# IcosaStellaMedallion.net
KiCad netlist of a schematic drawn in EAGLE
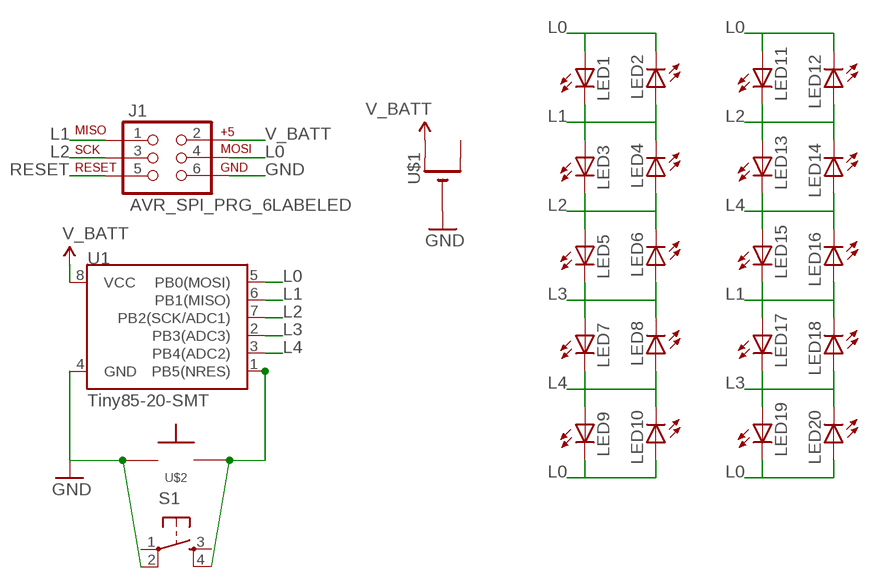
[diagram p0: schematic, sheet 1]

(export (version "E")
  (design (tool "Eeschema 10.0.6"))
  (components
    (comp (ref "J1")
      (value "AVR_SPI_PRG_6LABELED")
      (footprint "eagle-import:2X3-NS")
      (libsource (lib "eagle-import") (part "AVR_SPI_PRG_6LABELED"))
    )
    (comp (ref "LED1")
      (value "LED5MM")
      (footprint "eagle-import:LED5MM")
      (libsource (lib "eagle-import") (part "LED5MM"))
    )
    (comp (ref "LED2")
      (value "LED5MM")
      (footprint "eagle-import:LED5MM")
      (libsource (lib "eagle-import") (part "LED5MM"))
    )
    (comp (ref "LED3")
      (value "LED5MM")
      (footprint "eagle-import:LED5MM")
      (libsource (lib "eagle-import") (part "LED5MM"))
    )
    (comp (ref "LED4")
      (value "LED5MM")
      (footprint "eagle-import:LED5MM")
      (libsource (lib "eagle-import") (part "LED5MM"))
    )
    (comp (ref "LED5")
      (value "LED5MM")
      (footprint "eagle-import:LED5MM")
      (libsource (lib "eagle-import") (part "LED5MM"))
    )
    (comp (ref "LED6")
      (value "LED5MM")
      (footprint "eagle-import:LED5MM")
      (libsource (lib "eagle-import") (part "LED5MM"))
    )
    (comp (ref "LED7")
      (value "LED5MM")
      (footprint "eagle-import:LED5MM")
      (libsource (lib "eagle-import") (part "LED5MM"))
    )
    (comp (ref "LED8")
      (value "LED5MM")
      (footprint "eagle-import:LED5MM")
      (libsource (lib "eagle-import") (part "LED5MM"))
    )
    (comp (ref "LED9")
      (value "LED5MM")
      (footprint "eagle-import:LED5MM")
      (libsource (lib "eagle-import") (part "LED5MM"))
    )
    (comp (ref "LED10")
      (value "LED5MM")
      (footprint "eagle-import:LED5MM")
      (libsource (lib "eagle-import") (part "LED5MM"))
    )
    (comp (ref "LED11")
      (value "LED5MM")
      (footprint "eagle-import:LED5MM")
      (libsource (lib "eagle-import") (part "LED5MM"))
    )
    (comp (ref "LED12")
      (value "LED5MM")
      (footprint "eagle-import:LED5MM")
      (libsource (lib "eagle-import") (part "LED5MM"))
    )
    (comp (ref "LED13")
      (value "LED5MM")
      (footprint "eagle-import:LED5MM")
      (libsource (lib "eagle-import") (part "LED5MM"))
    )
    (comp (ref "LED14")
      (value "LED5MM")
      (footprint "eagle-import:LED5MM")
      (libsource (lib "eagle-import") (part "LED5MM"))
    )
    (comp (ref "LED15")
      (value "LED5MM")
      (footprint "eagle-import:LED5MM")
      (libsource (lib "eagle-import") (part "LED5MM"))
    )
    (comp (ref "LED16")
      (value "LED5MM")
      (footprint "eagle-import:LED5MM")
      (libsource (lib "eagle-import") (part "LED5MM"))
    )
    (comp (ref "LED17")
      (value "LED5MM")
      (footprint "eagle-import:LED5MM")
      (libsource (lib "eagle-import") (part "LED5MM"))
    )
    (comp (ref "LED18")
      (value "LED5MM")
      (footprint "eagle-import:LED5MM")
      (libsource (lib "eagle-import") (part "LED5MM"))
    )
    (comp (ref "LED19")
      (value "LED5MM")
      (footprint "eagle-import:LED5MM")
      (libsource (lib "eagle-import") (part "LED5MM"))
    )
    (comp (ref "LED20")
      (value "LED5MM")
      (footprint "eagle-import:LED5MM")
      (libsource (lib "eagle-import") (part "LED5MM"))
    )
    (comp (ref "S1")
      (value "TAC_SWITCHSMD")
      (footprint "eagle-import:TACTILE-SWITCH-SMD")
      (libsource (lib "eagle-import") (part "TAC_SWITCHSMD"))
    )
    (comp (ref "U$1")
      (value "CR2032THM")
      (footprint "eagle-import:CR2032-THRU")
      (libsource (lib "eagle-import") (part "CR2032THM"))
    )
    (comp (ref "U$2")
      (value "TAC_SPST_NOSMD")
      (footprint "eagle-import:KXT")
      (libsource (lib "eagle-import") (part "TAC_SPST_NOSMD"))
    )
    (comp (ref "U1")
      (value "Tiny85-20-SMT")
      (footprint "eagle-import:SO08-EIAJ")
      (libsource (lib "eagle-import") (part "ATTINY45TINY85-20-SMT"))
    )
  )
  (nets
    (net (code "1") (name "/L0") (class "Default")
      (node (ref "J1") (pin "4") (pinfunction "MOSI_4") (pintype "passive"))
      (node (ref "LED1") (pin "A") (pinfunction "A_A") (pintype "passive"))
      (node (ref "LED10") (pin "A") (pinfunction "A_A") (pintype "passive"))
      (node (ref "LED11") (pin "A") (pinfunction "A_A") (pintype "passive"))
      (node (ref "LED12") (pin "K") (pinfunction "C_K") (pintype "passive"))
      (node (ref "LED19") (pin "K") (pinfunction "C_K") (pintype "passive"))
      (node (ref "LED2") (pin "K") (pinfunction "C_K") (pintype "passive"))
      (node (ref "LED20") (pin "A") (pinfunction "A_A") (pintype "passive"))
      (node (ref "LED9") (pin "K") (pinfunction "C_K") (pintype "passive"))
      (node (ref "U1") (pin "5") (pinfunction "PB0(MOSI)_5") (pintype "bidirectional"))
    )
    (net (code "2") (name "/L1") (class "Default")
      (node (ref "J1") (pin "1") (pinfunction "MISO_1") (pintype "passive"))
      (node (ref "LED1") (pin "K") (pinfunction "C_K") (pintype "passive"))
      (node (ref "LED15") (pin "K") (pinfunction "C_K") (pintype "passive"))
      (node (ref "LED16") (pin "A") (pinfunction "A_A") (pintype "passive"))
      (node (ref "LED17") (pin "A") (pinfunction "A_A") (pintype "passive"))
      (node (ref "LED18") (pin "K") (pinfunction "C_K") (pintype "passive"))
      (node (ref "LED2") (pin "A") (pinfunction "A_A") (pintype "passive"))
      (node (ref "LED3") (pin "A") (pinfunction "A_A") (pintype "passive"))
      (node (ref "LED4") (pin "K") (pinfunction "C_K") (pintype "passive"))
      (node (ref "U1") (pin "6") (pinfunction "PB1(MISO)_6") (pintype "bidirectional"))
    )
    (net (code "3") (name "/L2") (class "Default")
      (node (ref "J1") (pin "3") (pinfunction "SCK_3") (pintype "passive"))
      (node (ref "LED11") (pin "K") (pinfunction "C_K") (pintype "passive"))
      (node (ref "LED12") (pin "A") (pinfunction "A_A") (pintype "passive"))
      (node (ref "LED13") (pin "A") (pinfunction "A_A") (pintype "passive"))
      (node (ref "LED14") (pin "K") (pinfunction "C_K") (pintype "passive"))
      (node (ref "LED3") (pin "K") (pinfunction "C_K") (pintype "passive"))
      (node (ref "LED4") (pin "A") (pinfunction "A_A") (pintype "passive"))
      (node (ref "LED5") (pin "A") (pinfunction "A_A") (pintype "passive"))
      (node (ref "LED6") (pin "K") (pinfunction "C_K") (pintype "passive"))
      (node (ref "U1") (pin "7") (pinfunction "PB2(SCK/ADC1)_7") (pintype "bidirectional"))
    )
    (net (code "4") (name "/L3") (class "Default")
      (node (ref "LED17") (pin "K") (pinfunction "C_K") (pintype "passive"))
      (node (ref "LED18") (pin "A") (pinfunction "A_A") (pintype "passive"))
      (node (ref "LED19") (pin "A") (pinfunction "A_A") (pintype "passive"))
      (node (ref "LED20") (pin "K") (pinfunction "C_K") (pintype "passive"))
      (node (ref "LED5") (pin "K") (pinfunction "C_K") (pintype "passive"))
      (node (ref "LED6") (pin "A") (pinfunction "A_A") (pintype "passive"))
      (node (ref "LED7") (pin "A") (pinfunction "A_A") (pintype "passive"))
      (node (ref "LED8") (pin "K") (pinfunction "C_K") (pintype "passive"))
      (node (ref "U1") (pin "2") (pinfunction "PB3(ADC3)_2") (pintype "bidirectional"))
    )
    (net (code "5") (name "/L4") (class "Default")
      (node (ref "LED10") (pin "K") (pinfunction "C_K") (pintype "passive"))
      (node (ref "LED13") (pin "K") (pinfunction "C_K") (pintype "passive"))
      (node (ref "LED14") (pin "A") (pinfunction "A_A") (pintype "passive"))
      (node (ref "LED15") (pin "A") (pinfunction "A_A") (pintype "passive"))
      (node (ref "LED16") (pin "K") (pinfunction "C_K") (pintype "passive"))
      (node (ref "LED7") (pin "K") (pinfunction "C_K") (pintype "passive"))
      (node (ref "LED8") (pin "A") (pinfunction "A_A") (pintype "passive"))
      (node (ref "LED9") (pin "A") (pinfunction "A_A") (pintype "passive"))
      (node (ref "U1") (pin "3") (pinfunction "PB4(ADC2)_3") (pintype "bidirectional"))
    )
    (net (code "6") (name "/RESET") (class "Default")
      (node (ref "J1") (pin "5") (pinfunction "RST_5") (pintype "passive"))
      (node (ref "S1") (pin "4") (pinfunction "4_4") (pintype "passive"))
      (node (ref "U$2") (pin "2") (pinfunction "P$2_2") (pintype "bidirectional"))
      (node (ref "U1") (pin "1") (pinfunction "PB5(NRES)_1") (pintype "bidirectional"))
    )
    (net (code "7") (name "GND") (class "Default")
      (node (ref "J1") (pin "6") (pinfunction "GND_6") (pintype "passive"))
      (node (ref "S1") (pin "2") (pinfunction "2_2") (pintype "passive"))
      (node (ref "U$1") (pin "-") (pinfunction "-_-") (pintype "passive"))
      (node (ref "U$2") (pin "1") (pinfunction "P$1_1") (pintype "bidirectional"))
      (node (ref "U1") (pin "4") (pinfunction "GND_4") (pintype "bidirectional"))
    )
    (net (code "8") (name "V_BATT") (class "Default")
      (node (ref "J1") (pin "2") (pinfunction "V+_2") (pintype "passive"))
      (node (ref "U$1") (pin "+1") (pinfunction "+_+1") (pintype "passive"))
      (node (ref "U1") (pin "8") (pinfunction "VCC_8") (pintype "bidirectional"))
    )
    (net (code "9") (name "unconnected-(S1-Pad1)") (class "Default")
      (node (ref "S1") (pin "1") (pinfunction "1_1") (pintype "passive"))
    )
    (net (code "10") (name "unconnected-(S1-Pad3)") (class "Default")
      (node (ref "S1") (pin "3") (pinfunction "3_3") (pintype "passive"))
    )
    (net (code "11") (name "unconnected-(U$1-+1-Pad+2)") (class "Default")
      (node (ref "U$1") (pin "+2") (pinfunction "+1_+2") (pintype "passive"))
    )
  )
)
